# 1Sheeld_Plus_Schematics_v1_0_0.net
KiCad netlist of a schematic drawn in EAGLE
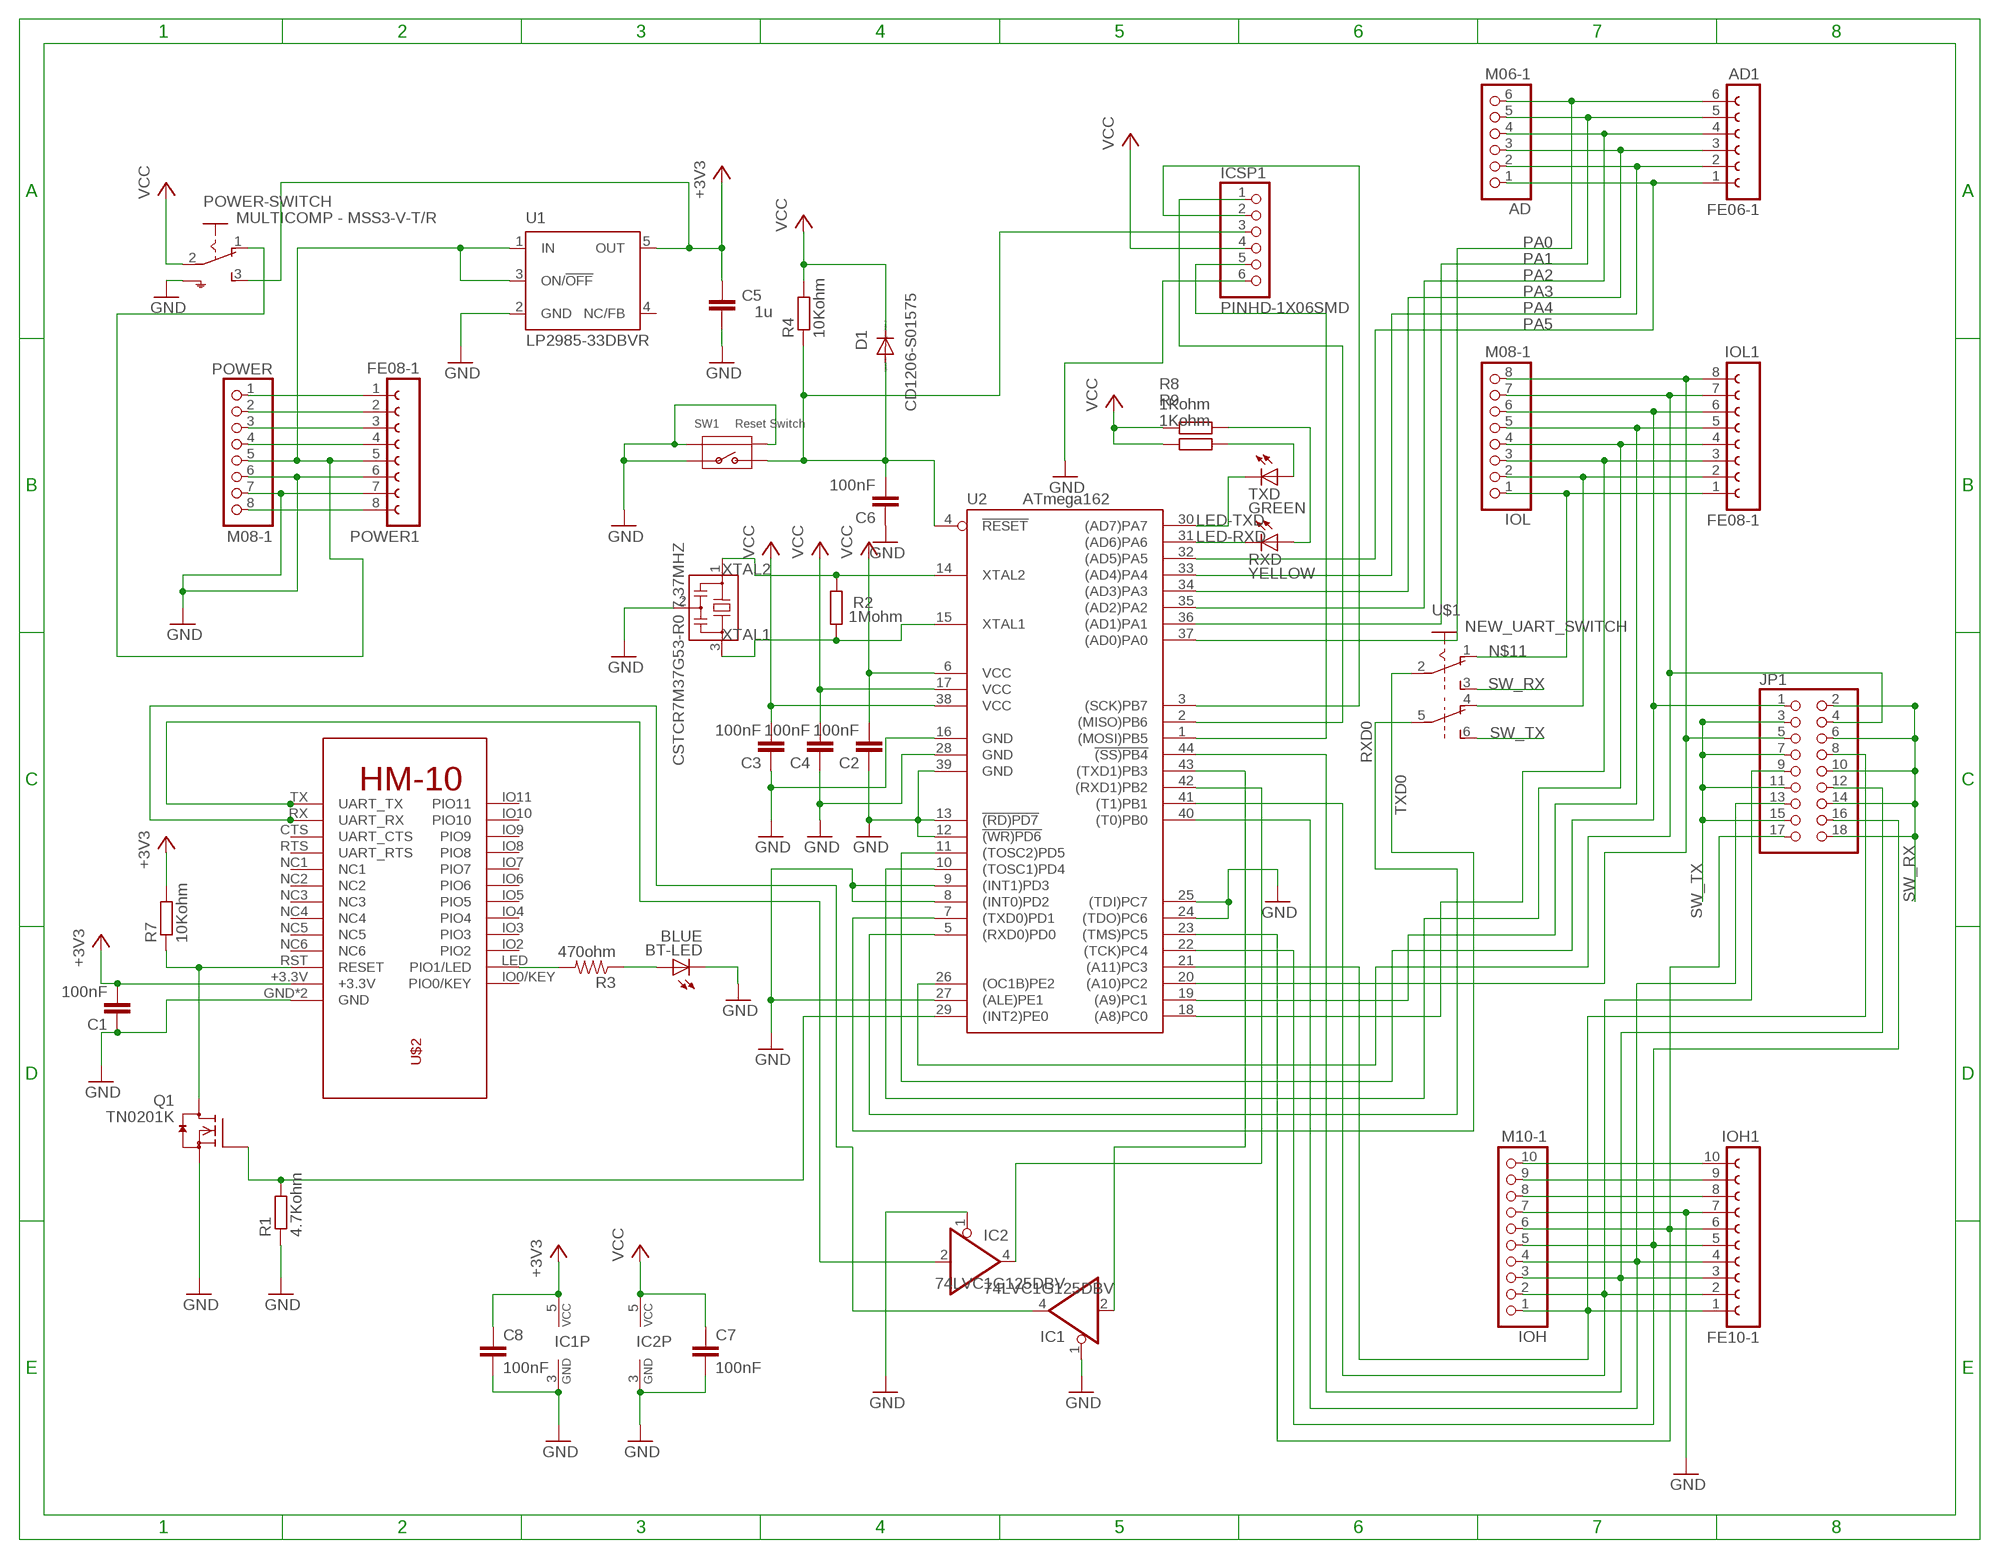
[diagram p0: schematic, sheet 1]

(export (version "E")
  (design (tool "Eeschema 10.0.6"))
  (components
    (comp (ref "AD")
      (value "M06-1")
      (footprint "eagle-import:1X06")
      (libsource (lib "eagle-import") (part "PINHD-1X6"))
    )
    (comp (ref "AD1")
      (value "FE06-1")
      (footprint "eagle-import:FE06")
      (libsource (lib "eagle-import") (part "FE06-1"))
    )
    (comp (ref "BT-LED")
      (value "BLUE")
      (footprint "eagle-import:CHIP-LED0805")
      (libsource (lib "eagle-import") (part "LEDCHIP-LED0805"))
    )
    (comp (ref "C1")
      (value "100nF")
      (footprint "eagle-import:C0603-ROUND")
      (libsource (lib "eagle-import") (part "C-EU0603-RND"))
    )
    (comp (ref "C2")
      (value "100nF")
      (footprint "eagle-import:C0603-ROUND")
      (libsource (lib "eagle-import") (part "C-EU0603-RND"))
    )
    (comp (ref "C3")
      (value "100nF")
      (footprint "eagle-import:C0603-ROUND")
      (libsource (lib "eagle-import") (part "C-EU0603-RND"))
    )
    (comp (ref "C4")
      (value "100nF")
      (footprint "eagle-import:C0603-ROUND")
      (libsource (lib "eagle-import") (part "C-EU0603-RND"))
    )
    (comp (ref "C5")
      (value "1u")
      (footprint "eagle-import:C0603-ROUND")
      (libsource (lib "eagle-import") (part "C-EU0603-RND"))
    )
    (comp (ref "C6")
      (value "100nF")
      (footprint "eagle-import:C0603-ROUND")
      (libsource (lib "eagle-import") (part "C-EU0603-RND"))
    )
    (comp (ref "C7")
      (value "100nF")
      (footprint "eagle-import:C0402")
      (libsource (lib "eagle-import") (part "C-EUC0402"))
    )
    (comp (ref "C8")
      (value "100nF")
      (footprint "eagle-import:C0402")
      (libsource (lib "eagle-import") (part "C-EUC0402"))
    )
    (comp (ref "D1")
      (value "CD1206-S01575")
      (footprint "eagle-import:MINIMELF")
      (libsource (lib "eagle-import") (part "DIODE-MINIMELF"))
    )
    (comp (ref "IC1")
      (value "74LVC1G125DBV")
      (footprint "eagle-import:SOT23-5")
      (libsource (lib "eagle-import") (part "741G125DBVLVC"))
    )
    (comp (ref "IC2")
      (value "74LVC1G125DBV")
      (footprint "eagle-import:SOT23-5")
      (libsource (lib "eagle-import") (part "741G125DBVLVC"))
    )
    (comp (ref "ICSP1")
      (value "PINHD-1X06SMD")
      (footprint "eagle-import:1X06_90SMD")
      (libsource (lib "eagle-import") (part "PINHD-1X06SMD"))
    )
    (comp (ref "IOH")
      (value "M10-1")
      (footprint "eagle-import:1X10")
      (libsource (lib "eagle-import") (part "PINHD-1X10_ARD"))
    )
    (comp (ref "IOH1")
      (value "FE10-1")
      (footprint "eagle-import:FE10")
      (libsource (lib "eagle-import") (part "FE10-1"))
    )
    (comp (ref "IOL")
      (value "M08-1")
      (footprint "eagle-import:1X08")
      (libsource (lib "eagle-import") (part "PINHD-1X8"))
    )
    (comp (ref "IOL1")
      (value "FE08-1")
      (footprint "eagle-import:FE08")
      (libsource (lib "eagle-import") (part "FE08-1"))
    )
    (comp (ref "JP1")
      (value "PINHD-2X9")
      (footprint "eagle-import:2X09")
      (libsource (lib "eagle-import") (part "PINHD-2X9"))
    )
    (comp (ref "POWER")
      (value "M08-1")
      (footprint "eagle-import:1X08")
      (libsource (lib "eagle-import") (part "PINHD-1X8"))
    )
    (comp (ref "POWER-SWITCH")
      (value "MULTICOMP - MSS3-V-T/R")
      (footprint "eagle-import:SWITCHMULTI")
      (libsource (lib "eagle-import") (part "SWITCHMULTI"))
    )
    (comp (ref "POWER1")
      (value "FE08-1")
      (footprint "eagle-import:FE08")
      (libsource (lib "eagle-import") (part "FE08-1"))
    )
    (comp (ref "Q1")
      (value "TN0201K")
      (footprint "eagle-import:SOT23")
      (libsource (lib "eagle-import") (part "TN0201K"))
    )
    (comp (ref "R1")
      (value "4.7Kohm")
      (footprint "eagle-import:M0805")
      (libsource (lib "eagle-import") (part "rcl_R-EU_M0805"))
    )
    (comp (ref "R2")
      (value "1Mohm")
      (footprint "eagle-import:R0603-ROUND")
      (libsource (lib "eagle-import") (part "R-EU_R0603"))
    )
    (comp (ref "R3")
      (value "470ohm")
      (footprint "eagle-import:0402-RES")
      (libsource (lib "eagle-import") (part "RESISTOR0402-RES"))
    )
    (comp (ref "R4")
      (value "10Kohm")
      (footprint "eagle-import:M0805")
      (libsource (lib "eagle-import") (part "rcl_R-EU_M0805"))
    )
    (comp (ref "R7")
      (value "10Kohm")
      (footprint "eagle-import:M0805")
      (libsource (lib "eagle-import") (part "rcl_R-EU_M0805"))
    )
    (comp (ref "R8")
      (value "1Kohm")
      (footprint "eagle-import:R0603-ROUND")
      (libsource (lib "eagle-import") (part "R-EU_R0603"))
    )
    (comp (ref "R9")
      (value "1Kohm")
      (footprint "eagle-import:R0603-ROUND")
      (libsource (lib "eagle-import") (part "R-EU_R0603"))
    )
    (comp (ref "RXD")
      (value "YELLOW")
      (footprint "eagle-import:CHIP-LED0805")
      (libsource (lib "eagle-import") (part "LEDCHIP-LED0805"))
    )
    (comp (ref "SW1")
      (value "Reset Switch")
      (footprint "eagle-import:DISCRETE_4P-SMD-7X3.5X3.5H")
      (libsource (lib "eagle-import") (part "DISCRETE_BUTTON-4P-REINFORCETS-1188E"))
    )
    (comp (ref "TXD")
      (value "GREEN")
      (footprint "eagle-import:CHIP-LED0805")
      (libsource (lib "eagle-import") (part "LEDCHIP-LED0805"))
    )
    (comp (ref "U$1")
      (value "NEW_UART_SWITCH")
      (footprint "eagle-import:NEW_UART_SWITCH")
      (libsource (lib "eagle-import") (part "NEW_UART_SWITCH"))
    )
    (comp (ref "U$2")
      (value "HM-10")
      (footprint "eagle-import:HM-10")
      (libsource (lib "eagle-import") (part "HM-10"))
    )
    (comp (ref "U1")
      (value "LP2985-33DBVR")
      (footprint "eagle-import:SOT23-DBV")
      (libsource (lib "eagle-import") (part "LP2985-XXDBVR33"))
    )
    (comp (ref "U2")
      (value "ATmega162")
      (footprint "eagle-import:TQFP44")
      (libsource (lib "eagle-import") (part "ATMEGA162"))
    )
    (comp (ref "Y1")
      (value "CSTCR7M37G53-R0 7.37MHZ")
      (footprint "eagle-import:CSTCR6M")
      (fields (field (name "MPN") "CSTCR6M00G53-R0"))
      (libsource (lib "eagle-import") (part "CSTCR6M00G53Z"))
    )
  )
  (nets
    (net (code "1") (name "+3V3") (class "Default")
      (node (ref "C1") (pin "2") (pinfunction "2_2") (pintype "passive"))
      (node (ref "C5") (pin "2") (pinfunction "2_2") (pintype "passive"))
      (node (ref "C8") (pin "1") (pinfunction "1_1") (pintype "passive"))
      (node (ref "IC1") (pin "5") (pinfunction "VCC_5") (pintype "power_in"))
      (node (ref "POWER-SWITCH") (pin "3") (pinfunction "S_3") (pintype "passive"))
      (node (ref "R7") (pin "2") (pinfunction "2_2") (pintype "passive"))
      (node (ref "U$2") (pin "+3.3V") (pinfunction "+3.3V_+3.3V") (pintype "bidirectional"))
      (node (ref "U1") (pin "5") (pinfunction "OUT_5") (pintype "passive"))
    )
    (net (code "2") (name "/LED-RXD") (class "Default")
      (node (ref "RXD") (pin "C") (pinfunction "C_C") (pintype "passive"))
      (node (ref "U2") (pin "31") (pinfunction "(AD6)PA6_31") (pintype "bidirectional"))
    )
    (net (code "3") (name "/LED-TXD") (class "Default")
      (node (ref "TXD") (pin "C") (pinfunction "C_C") (pintype "passive"))
      (node (ref "U2") (pin "30") (pinfunction "(AD7)PA7_30") (pintype "bidirectional"))
    )
    (net (code "4") (name "/N$11") (class "Default")
      (node (ref "IOL") (pin "1") (pinfunction "1_1") (pintype "passive"))
      (node (ref "IOL1") (pin "1") (pinfunction "1_1") (pintype "passive"))
      (node (ref "U$1") (pin "1") (pinfunction "1_1") (pintype "passive"))
    )
    (net (code "5") (name "/PA0") (class "Default")
      (node (ref "AD") (pin "6") (pinfunction "6_6") (pintype "passive"))
      (node (ref "AD1") (pin "6") (pinfunction "6_6") (pintype "passive"))
      (node (ref "U2") (pin "37") (pinfunction "(AD0)PA0_37") (pintype "bidirectional"))
    )
    (net (code "6") (name "/PA1") (class "Default")
      (node (ref "AD") (pin "5") (pinfunction "5_5") (pintype "passive"))
      (node (ref "AD1") (pin "5") (pinfunction "5_5") (pintype "passive"))
      (node (ref "U2") (pin "36") (pinfunction "(AD1)PA1_36") (pintype "bidirectional"))
    )
    (net (code "7") (name "/PA2") (class "Default")
      (node (ref "AD") (pin "4") (pinfunction "4_4") (pintype "passive"))
      (node (ref "AD1") (pin "4") (pinfunction "4_4") (pintype "passive"))
      (node (ref "U2") (pin "35") (pinfunction "(AD2)PA2_35") (pintype "bidirectional"))
    )
    (net (code "8") (name "/PA3") (class "Default")
      (node (ref "AD") (pin "3") (pinfunction "3_3") (pintype "passive"))
      (node (ref "AD1") (pin "3") (pinfunction "3_3") (pintype "passive"))
      (node (ref "U2") (pin "34") (pinfunction "(AD3)PA3_34") (pintype "bidirectional"))
    )
    (net (code "9") (name "/PA4") (class "Default")
      (node (ref "AD") (pin "2") (pinfunction "2_2") (pintype "passive"))
      (node (ref "AD1") (pin "2") (pinfunction "2_2") (pintype "passive"))
      (node (ref "U2") (pin "33") (pinfunction "(AD4)PA4_33") (pintype "bidirectional"))
    )
    (net (code "10") (name "/PA5") (class "Default")
      (node (ref "AD") (pin "1") (pinfunction "1_1") (pintype "passive"))
      (node (ref "AD1") (pin "1") (pinfunction "1_1") (pintype "passive"))
      (node (ref "U2") (pin "32") (pinfunction "(AD5)PA5_32") (pintype "bidirectional"))
    )
    (net (code "11") (name "/RXD0") (class "Default")
      (node (ref "U$1") (pin "5") (pinfunction "5_5") (pintype "passive"))
      (node (ref "U2") (pin "5") (pinfunction "(RXD0)PD0_5") (pintype "bidirectional"))
    )
    (net (code "12") (name "/SW_RX") (class "Default")
      (node (ref "JP1") (pin "10") (pinfunction "10_10") (pintype "passive"))
      (node (ref "JP1") (pin "14") (pinfunction "14_14") (pintype "passive"))
      (node (ref "JP1") (pin "18") (pinfunction "18_18") (pintype "passive"))
      (node (ref "JP1") (pin "2") (pinfunction "2_2") (pintype "passive"))
      (node (ref "JP1") (pin "6") (pinfunction "6_6") (pintype "passive"))
      (node (ref "U$1") (pin "3") (pinfunction "3_3") (pintype "passive"))
    )
    (net (code "13") (name "/SW_TX") (class "Default")
      (node (ref "JP1") (pin "11") (pinfunction "11_11") (pintype "passive"))
      (node (ref "JP1") (pin "15") (pinfunction "15_15") (pintype "passive"))
      (node (ref "JP1") (pin "3") (pinfunction "3_3") (pintype "passive"))
      (node (ref "JP1") (pin "7") (pinfunction "7_7") (pintype "passive"))
      (node (ref "U$1") (pin "6") (pinfunction "6_6") (pintype "passive"))
    )
    (net (code "14") (name "/TXD0") (class "Default")
      (node (ref "U$1") (pin "2") (pinfunction "2_2") (pintype "passive"))
      (node (ref "U2") (pin "7") (pinfunction "(TXD0)PD1_7") (pintype "bidirectional"))
    )
    (net (code "15") (name "/XTAL1") (class "Default")
      (node (ref "R2") (pin "1") (pinfunction "1_1") (pintype "passive"))
      (node (ref "U2") (pin "15") (pinfunction "XTAL1_15") (pintype "input"))
      (node (ref "Y1") (pin "3") (pinfunction "3_3") (pintype "passive"))
    )
    (net (code "16") (name "/XTAL2") (class "Default")
      (node (ref "R2") (pin "2") (pinfunction "2_2") (pintype "passive"))
      (node (ref "U2") (pin "14") (pinfunction "XTAL2_14") (pintype "input"))
      (node (ref "Y1") (pin "1") (pinfunction "1_1") (pintype "passive"))
    )
    (net (code "17") (name "GND") (class "Default")
      (node (ref "BT-LED") (pin "C") (pinfunction "C_C") (pintype "passive"))
      (node (ref "C1") (pin "1") (pinfunction "1_1") (pintype "passive"))
      (node (ref "C2") (pin "1") (pinfunction "1_1") (pintype "passive"))
      (node (ref "C3") (pin "1") (pinfunction "1_1") (pintype "passive"))
      (node (ref "C4") (pin "1") (pinfunction "1_1") (pintype "passive"))
      (node (ref "C5") (pin "1") (pinfunction "1_1") (pintype "passive"))
      (node (ref "C6") (pin "1") (pinfunction "1_1") (pintype "passive"))
      (node (ref "C7") (pin "2") (pinfunction "2_2") (pintype "passive"))
      (node (ref "C8") (pin "2") (pinfunction "2_2") (pintype "passive"))
      (node (ref "IC1") (pin "1") (pinfunction "OE_1") (pintype "input"))
      (node (ref "IC1") (pin "3") (pinfunction "GND_3") (pintype "power_in"))
      (node (ref "IC2") (pin "1") (pinfunction "OE_1") (pintype "input"))
      (node (ref "IC2") (pin "3") (pinfunction "GND_3") (pintype "power_in"))
      (node (ref "ICSP1") (pin "6") (pinfunction "6_6") (pintype "passive"))
      (node (ref "IOH") (pin "7") (pinfunction "7_7") (pintype "passive"))
      (node (ref "IOH1") (pin "7") (pinfunction "7_7") (pintype "passive"))
      (node (ref "POWER") (pin "6") (pinfunction "6_6") (pintype "passive"))
      (node (ref "POWER") (pin "7") (pinfunction "7_7") (pintype "passive"))
      (node (ref "POWER-SWITCH") (pin "P$4") (pinfunction "SH_P$4") (pintype "passive"))
      (node (ref "POWER-SWITCH") (pin "P$5") (pinfunction "SH_P$5") (pintype "passive"))
      (node (ref "POWER-SWITCH") (pin "P$6") (pinfunction "SH_P$6") (pintype "passive"))
      (node (ref "POWER-SWITCH") (pin "P$7") (pinfunction "SH_P$7") (pintype "passive"))
      (node (ref "POWER1") (pin "6") (pinfunction "6_6") (pintype "passive"))
      (node (ref "POWER1") (pin "7") (pinfunction "7_7") (pintype "passive"))
      (node (ref "Q1") (pin "2") (pinfunction "S_2") (pintype "passive"))
      (node (ref "R1") (pin "1") (pinfunction "1_1") (pintype "passive"))
      (node (ref "SW1") (pin "1") (pinfunction "1_1") (pintype "bidirectional"))
      (node (ref "SW1") (pin "S1") (pinfunction "S1_S1") (pintype "bidirectional"))
      (node (ref "SW1") (pin "S2") (pinfunction "S2_S2") (pintype "bidirectional"))
      (node (ref "U$2") (pin "GND") (pinfunction "GND_GND") (pintype "bidirectional"))
      (node (ref "U$2") (pin "GND2") (pinfunction "GND_GND2") (pintype "bidirectional"))
      (node (ref "U1") (pin "2") (pinfunction "GND_2") (pintype "power_in"))
      (node (ref "U2") (pin "12") (pinfunction "~{(WR})PD6_12") (pintype "bidirectional"))
      (node (ref "U2") (pin "13") (pinfunction "~{(RD})PD7_13") (pintype "bidirectional"))
      (node (ref "U2") (pin "16") (pinfunction "GND_16") (pintype "power_in"))
      (node (ref "U2") (pin "24") (pinfunction "(TDO)PC6_24") (pintype "bidirectional"))
      (node (ref "U2") (pin "25") (pinfunction "(TDI)PC7_25") (pintype "bidirectional"))
      (node (ref "U2") (pin "27") (pinfunction "(ALE)PE1_27") (pintype "bidirectional"))
      (node (ref "U2") (pin "28") (pinfunction "GND_28") (pintype "power_in"))
      (node (ref "U2") (pin "39") (pinfunction "GND_39") (pintype "power_in"))
      (node (ref "U2") (pin "8") (pinfunction "(INT0)PD2_8") (pintype "bidirectional"))
      (node (ref "U2") (pin "9") (pinfunction "(INT1)PD3_9") (pintype "bidirectional"))
      (node (ref "Y1") (pin "2") (pinfunction "2_2") (pintype "passive"))
    )
    (net (code "18") (name "Net-(BT-LED-PadA)") (class "Default")
      (node (ref "BT-LED") (pin "A") (pinfunction "A_A") (pintype "passive"))
      (node (ref "R3") (pin "1") (pinfunction "1_1") (pintype "passive"))
    )
    (net (code "19") (name "Net-(IC1A-I)") (class "Default")
      (node (ref "IC1") (pin "2") (pinfunction "I_2") (pintype "input"))
      (node (ref "U2") (pin "43") (pinfunction "(TXD1)PB3_43") (pintype "bidirectional"))
    )
    (net (code "20") (name "Net-(IC1A-O)") (class "Default")
      (node (ref "IC1") (pin "4") (pinfunction "O_4") (pintype "tri_state"))
      (node (ref "U$2") (pin "RX") (pinfunction "UART_RX_RX") (pintype "bidirectional"))
    )
    (net (code "21") (name "Net-(IC2A-I)") (class "Default")
      (node (ref "IC2") (pin "2") (pinfunction "I_2") (pintype "input"))
      (node (ref "U$2") (pin "TX") (pinfunction "UART_TX_TX") (pintype "bidirectional"))
    )
    (net (code "22") (name "Net-(IC2A-O)") (class "Default")
      (node (ref "IC2") (pin "4") (pinfunction "O_4") (pintype "tri_state"))
      (node (ref "U2") (pin "42") (pinfunction "(RXD1)PB2_42") (pintype "bidirectional"))
    )
    (net (code "23") (name "Net-(IOH-Pad8)") (class "Default")
      (node (ref "IOH") (pin "8") (pinfunction "8_8") (pintype "passive"))
      (node (ref "IOH1") (pin "8") (pinfunction "8_8") (pintype "passive"))
    )
    (net (code "24") (name "Net-(IOH-Pad9)") (class "Default")
      (node (ref "IOH") (pin "9") (pinfunction "9_9") (pintype "passive"))
      (node (ref "IOH1") (pin "9") (pinfunction "9_9") (pintype "passive"))
    )
    (net (code "25") (name "Net-(IOH-Pad10)") (class "Default")
      (node (ref "IOH") (pin "10") (pinfunction "10_10") (pintype "passive"))
      (node (ref "IOH1") (pin "10") (pinfunction "10_10") (pintype "passive"))
    )
    (net (code "26") (name "Net-(IOL-Pad2)") (class "Default")
      (node (ref "IOL") (pin "2") (pinfunction "2_2") (pintype "passive"))
      (node (ref "IOL1") (pin "2") (pinfunction "2_2") (pintype "passive"))
      (node (ref "U$1") (pin "4") (pinfunction "4_4") (pintype "passive"))
    )
    (net (code "27") (name "Net-(POWER-Pad1)") (class "Default")
      (node (ref "POWER") (pin "1") (pinfunction "1_1") (pintype "passive"))
      (node (ref "POWER1") (pin "1") (pinfunction "1_1") (pintype "passive"))
    )
    (net (code "28") (name "Net-(POWER-Pad2)") (class "Default")
      (node (ref "POWER") (pin "2") (pinfunction "2_2") (pintype "passive"))
      (node (ref "POWER1") (pin "2") (pinfunction "2_2") (pintype "passive"))
    )
    (net (code "29") (name "Net-(POWER-Pad3)") (class "Default")
      (node (ref "POWER") (pin "3") (pinfunction "3_3") (pintype "passive"))
      (node (ref "POWER1") (pin "3") (pinfunction "3_3") (pintype "passive"))
    )
    (net (code "30") (name "Net-(POWER-Pad4)") (class "Default")
      (node (ref "POWER") (pin "4") (pinfunction "4_4") (pintype "passive"))
      (node (ref "POWER1") (pin "4") (pinfunction "4_4") (pintype "passive"))
    )
    (net (code "31") (name "Net-(POWER-Pad8)") (class "Default")
      (node (ref "POWER") (pin "8") (pinfunction "8_8") (pintype "passive"))
      (node (ref "POWER1") (pin "8") (pinfunction "8_8") (pintype "passive"))
    )
    (net (code "32") (name "Net-(POWER-SWITCH-O)") (class "Default")
      (node (ref "POWER") (pin "5") (pinfunction "5_5") (pintype "passive"))
      (node (ref "POWER-SWITCH") (pin "1") (pinfunction "O_1") (pintype "passive"))
      (node (ref "POWER1") (pin "5") (pinfunction "5_5") (pintype "passive"))
      (node (ref "U1") (pin "1") (pinfunction "IN_1") (pintype "input"))
      (node (ref "U1") (pin "3") (pinfunction "ON/~{OFF}_3") (pintype "input"))
    )
    (net (code "33") (name "Net-(Q1-D)") (class "Default")
      (node (ref "Q1") (pin "3") (pinfunction "D_3") (pintype "passive"))
      (node (ref "R7") (pin "1") (pinfunction "1_1") (pintype "passive"))
      (node (ref "U$2") (pin "RST") (pinfunction "RESET_RST") (pintype "bidirectional"))
    )
    (net (code "34") (name "Net-(Q1-G)") (class "Default")
      (node (ref "Q1") (pin "1") (pinfunction "G_1") (pintype "passive"))
      (node (ref "R1") (pin "2") (pinfunction "2_2") (pintype "passive"))
      (node (ref "U2") (pin "29") (pinfunction "(INT2)PE0_29") (pintype "bidirectional"))
    )
    (net (code "35") (name "Net-(R8-Pad1)") (class "Default")
      (node (ref "R8") (pin "1") (pinfunction "1_1") (pintype "passive"))
      (node (ref "RXD") (pin "A") (pinfunction "A_A") (pintype "passive"))
    )
    (net (code "36") (name "Net-(R9-Pad1)") (class "Default")
      (node (ref "R9") (pin "1") (pinfunction "1_1") (pintype "passive"))
      (node (ref "TXD") (pin "A") (pinfunction "A_A") (pintype "passive"))
    )
    (net (code "37") (name "Net-(U$2-PIO1{slash}LED)") (class "Default")
      (node (ref "R3") (pin "2") (pinfunction "2_2") (pintype "passive"))
      (node (ref "U$2") (pin "LED") (pinfunction "PIO1/LED_LED") (pintype "bidirectional"))
    )
    (net (code "38") (name "Net-(U2-(A8)PC0)") (class "Default")
      (node (ref "IOL") (pin "3") (pinfunction "3_3") (pintype "passive"))
      (node (ref "IOL1") (pin "3") (pinfunction "3_3") (pintype "passive"))
      (node (ref "U2") (pin "18") (pinfunction "(A8)PC0_18") (pintype "bidirectional"))
    )
    (net (code "39") (name "Net-(U2-(A9)PC1)") (class "Default")
      (node (ref "IOL") (pin "5") (pinfunction "5_5") (pintype "passive"))
      (node (ref "IOL1") (pin "5") (pinfunction "5_5") (pintype "passive"))
      (node (ref "U2") (pin "19") (pinfunction "(A9)PC1_19") (pintype "bidirectional"))
    )
    (net (code "40") (name "Net-(U2-(A10)PC2)") (class "Default")
      (node (ref "IOL") (pin "8") (pinfunction "8_8") (pintype "passive"))
      (node (ref "IOL1") (pin "8") (pinfunction "8_8") (pintype "passive"))
      (node (ref "JP1") (pin "5") (pinfunction "5_5") (pintype "passive"))
      (node (ref "U2") (pin "20") (pinfunction "(A10)PC2_20") (pintype "bidirectional"))
    )
    (net (code "41") (name "Net-(U2-(A11)PC3)") (class "Default")
      (node (ref "IOH") (pin "1") (pinfunction "1_1") (pintype "passive"))
      (node (ref "IOH1") (pin "1") (pinfunction "1_1") (pintype "passive"))
      (node (ref "JP1") (pin "8") (pinfunction "8_8") (pintype "passive"))
      (node (ref "U2") (pin "21") (pinfunction "(A11)PC3_21") (pintype "bidirectional"))
    )
    (net (code "42") (name "Net-(U2-(MISO)PB6)") (class "Default")
      (node (ref "ICSP1") (pin "1") (pinfunction "1_1") (pintype "passive"))
      (node (ref "U2") (pin "2") (pinfunction "(MISO)PB6_2") (pintype "bidirectional"))
    )
    (net (code "43") (name "Net-(U2-(MOSI)PB5)") (class "Default")
      (node (ref "ICSP1") (pin "5") (pinfunction "5_5") (pintype "passive"))
      (node (ref "U2") (pin "1") (pinfunction "(MOSI)PB5_1") (pintype "bidirectional"))
    )
    (net (code "44") (name "Net-(U2-(OC1B)PE2)") (class "Default")
      (node (ref "IOL") (pin "7") (pinfunction "7_7") (pintype "passive"))
      (node (ref "IOL1") (pin "7") (pinfunction "7_7") (pintype "passive"))
      (node (ref "JP1") (pin "4") (pinfunction "4_4") (pintype "passive"))
      (node (ref "U2") (pin "26") (pinfunction "(OC1B)PE2_26") (pintype "bidirectional"))
    )
    (net (code "45") (name "Net-(U2-(SCK)PB7)") (class "Default")
      (node (ref "ICSP1") (pin "2") (pinfunction "2_2") (pintype "passive"))
      (node (ref "U2") (pin "3") (pinfunction "(SCK)PB7_3") (pintype "bidirectional"))
    )
    (net (code "46") (name "Net-(U2-(T0)PB0)") (class "Default")
      (node (ref "IOH") (pin "4") (pinfunction "4_4") (pintype "passive"))
      (node (ref "IOH1") (pin "4") (pinfunction "4_4") (pintype "passive"))
      (node (ref "JP1") (pin "13") (pinfunction "13_13") (pintype "passive"))
      (node (ref "U2") (pin "40") (pinfunction "(T0)PB0_40") (pintype "bidirectional"))
    )
    (net (code "47") (name "Net-(U2-(T1)PB1)") (class "Default")
      (node (ref "IOH") (pin "2") (pinfunction "2_2") (pintype "passive"))
      (node (ref "IOH1") (pin "2") (pinfunction "2_2") (pintype "passive"))
      (node (ref "JP1") (pin "9") (pinfunction "9_9") (pintype "passive"))
      (node (ref "U2") (pin "41") (pinfunction "(T1)PB1_41") (pintype "bidirectional"))
    )
    (net (code "48") (name "Net-(U2-(TCK)PC4)") (class "Default")
      (node (ref "IOH") (pin "5") (pinfunction "5_5") (pintype "passive"))
      (node (ref "IOH1") (pin "5") (pinfunction "5_5") (pintype "passive"))
      (node (ref "JP1") (pin "16") (pinfunction "16_16") (pintype "passive"))
      (node (ref "U2") (pin "22") (pinfunction "(TCK)PC4_22") (pintype "bidirectional"))
    )
    (net (code "49") (name "Net-(U2-(TMS)PC5)") (class "Default")
      (node (ref "IOH") (pin "6") (pinfunction "6_6") (pintype "passive"))
      (node (ref "IOH1") (pin "6") (pinfunction "6_6") (pintype "passive"))
      (node (ref "JP1") (pin "17") (pinfunction "17_17") (pintype "passive"))
      (node (ref "U2") (pin "23") (pinfunction "(TMS)PC5_23") (pintype "bidirectional"))
    )
    (net (code "50") (name "Net-(U2-(TOSC1)PD4)") (class "Default")
      (node (ref "IOL") (pin "4") (pinfunction "4_4") (pintype "passive"))
      (node (ref "IOL1") (pin "4") (pinfunction "4_4") (pintype "passive"))
      (node (ref "U2") (pin "10") (pinfunction "(TOSC1)PD4_10") (pintype "bidirectional"))
    )
    (net (code "51") (name "Net-(U2-(TOSC2)PD5)") (class "Default")
      (node (ref "IOL") (pin "6") (pinfunction "6_6") (pintype "passive"))
      (node (ref "IOL1") (pin "6") (pinfunction "6_6") (pintype "passive"))
      (node (ref "JP1") (pin "1") (pinfunction "1_1") (pintype "passive"))
      (node (ref "U2") (pin "11") (pinfunction "(TOSC2)PD5_11") (pintype "bidirectional"))
    )
    (net (code "52") (name "Net-(U2-~{(SS})PB4)") (class "Default")
      (node (ref "IOH") (pin "3") (pinfunction "3_3") (pintype "passive"))
      (node (ref "IOH1") (pin "3") (pinfunction "3_3") (pintype "passive"))
      (node (ref "JP1") (pin "12") (pinfunction "12_12") (pintype "passive"))
      (node (ref "U2") (pin "44") (pinfunction "~{(SS})PB4_44") (pintype "bidirectional"))
    )
    (net (code "53") (name "Net-(U2-~{RESET})") (class "Default")
      (node (ref "C6") (pin "2") (pinfunction "2_2") (pintype "passive"))
      (node (ref "D1") (pin "A") (pinfunction "A_A") (pintype "passive"))
      (node (ref "ICSP1") (pin "3") (pinfunction "3_3") (pintype "passive"))
      (node (ref "R4") (pin "1") (pinfunction "1_1") (pintype "passive"))
      (node (ref "SW1") (pin "2") (pinfunction "2_2") (pintype "bidirectional"))
      (node (ref "U2") (pin "4") (pinfunction "~{RESET}_4") (pintype "input"))
    )
    (net (code "54") (name "VCC") (class "Default")
      (node (ref "C2") (pin "2") (pinfunction "2_2") (pintype "passive"))
      (node (ref "C3") (pin "2") (pinfunction "2_2") (pintype "passive"))
      (node (ref "C4") (pin "2") (pinfunction "2_2") (pintype "passive"))
      (node (ref "C7") (pin "1") (pinfunction "1_1") (pintype "passive"))
      (node (ref "D1") (pin "C") (pinfunction "C_C") (pintype "passive"))
      (node (ref "IC2") (pin "5") (pinfunction "VCC_5") (pintype "power_in"))
      (node (ref "ICSP1") (pin "4") (pinfunction "4_4") (pintype "passive"))
      (node (ref "POWER-SWITCH") (pin "2") (pinfunction "P_2") (pintype "passive"))
      (node (ref "R4") (pin "2") (pinfunction "2_2") (pintype "passive"))
      (node (ref "R8") (pin "2") (pinfunction "2_2") (pintype "passive"))
      (node (ref "R9") (pin "2") (pinfunction "2_2") (pintype "passive"))
      (node (ref "U2") (pin "17") (pinfunction "VCC_17") (pintype "power_in"))
      (node (ref "U2") (pin "38") (pinfunction "VCC_38") (pintype "power_in"))
      (node (ref "U2") (pin "6") (pinfunction "VCC_6") (pintype "power_in"))
    )
    (net (code "55") (name "unconnected-(U$2-PIO0{slash}KEY-PadIO0{slash}KEY)") (class "Default")
      (node (ref "U$2") (pin "IO0/KEY") (pinfunction "PIO0/KEY_IO0/KEY") (pintype "bidirectional"))
    )
    (net (code "56") (name "unconnected-(U$2-PIO2-PadIO2)") (class "Default")
      (node (ref "U$2") (pin "IO2") (pinfunction "PIO2_IO2") (pintype "bidirectional"))
    )
    (net (code "57") (name "unconnected-(U$2-PIO3-PadIO3)") (class "Default")
      (node (ref "U$2") (pin "IO3") (pinfunction "PIO3_IO3") (pintype "bidirectional"))
    )
    (net (code "58") (name "unconnected-(U$2-PIO4-PadIO4)") (class "Default")
      (node (ref "U$2") (pin "IO4") (pinfunction "PIO4_IO4") (pintype "bidirectional"))
    )
    (net (code "59") (name "unconnected-(U$2-PIO5-PadIO5)") (class "Default")
      (node (ref "U$2") (pin "IO5") (pinfunction "PIO5_IO5") (pintype "bidirectional"))
    )
    (net (code "60") (name "unconnected-(U$2-PIO6-PadIO6)") (class "Default")
      (node (ref "U$2") (pin "IO6") (pinfunction "PIO6_IO6") (pintype "bidirectional"))
    )
    (net (code "61") (name "unconnected-(U$2-PIO7-PadIO7)") (class "Default")
      (node (ref "U$2") (pin "IO7") (pinfunction "PIO7_IO7") (pintype "bidirectional"))
    )
    (net (code "62") (name "unconnected-(U$2-PIO8-PadIO8)") (class "Default")
      (node (ref "U$2") (pin "IO8") (pinfunction "PIO8_IO8") (pintype "bidirectional"))
    )
    (net (code "63") (name "unconnected-(U$2-PIO9-PadIO9)") (class "Default")
      (node (ref "U$2") (pin "IO9") (pinfunction "PIO9_IO9") (pintype "bidirectional"))
    )
    (net (code "64") (name "unconnected-(U$2-PIO10-PadIO10)") (class "Default")
      (node (ref "U$2") (pin "IO10") (pinfunction "PIO10_IO10") (pintype "bidirectional"))
    )
    (net (code "65") (name "unconnected-(U$2-PIO11-PadIO11)") (class "Default")
      (node (ref "U$2") (pin "IO11") (pinfunction "PIO11_IO11") (pintype "bidirectional"))
    )
    (net (code "66") (name "unconnected-(U$2-PadNC1)") (class "Default")
      (node (ref "U$2") (pin "NC1") (pinfunction "NC1_NC1") (pintype "bidirectional"))
    )
    (net (code "67") (name "unconnected-(U$2-PadNC2)") (class "Default")
      (node (ref "U$2") (pin "NC2") (pinfunction "NC2_NC2") (pintype "bidirectional"))
    )
    (net (code "68") (name "unconnected-(U$2-PadNC3)") (class "Default")
      (node (ref "U$2") (pin "NC3") (pinfunction "NC3_NC3") (pintype "bidirectional"))
    )
    (net (code "69") (name "unconnected-(U$2-PadNC4)") (class "Default")
      (node (ref "U$2") (pin "NC4") (pinfunction "NC4_NC4") (pintype "bidirectional"))
    )
    (net (code "70") (name "unconnected-(U$2-PadNC5)") (class "Default")
      (node (ref "U$2") (pin "NC5") (pinfunction "NC5_NC5") (pintype "bidirectional"))
    )
    (net (code "71") (name "unconnected-(U$2-PadNC6)") (class "Default")
      (node (ref "U$2") (pin "NC6") (pinfunction "NC6_NC6") (pintype "bidirectional"))
    )
    (net (code "72") (name "unconnected-(U$2-UART_CTS-PadCTS)") (class "Default")
      (node (ref "U$2") (pin "CTS") (pinfunction "UART_CTS_CTS") (pintype "bidirectional"))
    )
    (net (code "73") (name "unconnected-(U$2-UART_RTS-PadRTS)") (class "Default")
      (node (ref "U$2") (pin "RTS") (pinfunction "UART_RTS_RTS") (pintype "bidirectional"))
    )
    (net (code "74") (name "unconnected-(U1-NC{slash}FB-Pad4)") (class "Default")
      (node (ref "U1") (pin "4") (pinfunction "NC/FB_4") (pintype "passive"))
    )
  )
)
